# SOM_Resets_BootConfig.net
KiCad netlist of a schematic drawn in Altium Designer
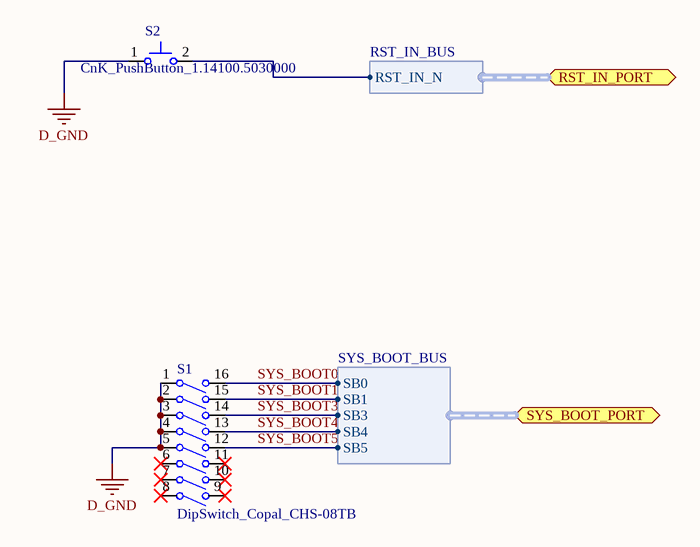
[diagram p0: SOM_Resets_BootConfig.SchDoc]

(export (version "E")
  (design (tool "Eeschema 10.0.6"))
  (components
    (comp (ref "S1")
      (value "DipSwitch_Copal_CHS-08TB")
      (footprint "SOP127P800X250-16N_DIP_SWITCH_COPAL:SOP127P800X250-16N_DIP_SWITCH_COPAL")
      (fields (field (name "PUBLISHER") "Altium Limited"))
      (libsource (lib "OMRON Switch DIP") (part "A6H-8102-P"))
    )
    (comp (ref "S2")
      (value "CnK_PushButton_1.14100.5030000")
      (footprint "SOP127P600-8N_PushButtonRacon8:SOP127P600-8N_PushButtonRacon8")
      (fields (field (name "PUBLISHER") "Altium Limited"))
      (libsource (lib "CK Switch") (part "KSS222GLFG"))
    )
  )
  (nets
    (net (code "3") (name "/RST_IN_N") (class "Default")
      (node (ref "S2") (pin "2") (pinfunction "2_2") (pintype "passive"))
    )
    (net (code "4") (name "/SYS_BOOT0") (class "Default")
      (node (ref "S1") (pin "16") (pinfunction "B1_16") (pintype "passive"))
    )
    (net (code "5") (name "/SYS_BOOT1") (class "Default")
      (node (ref "S1") (pin "15") (pinfunction "B2_15") (pintype "passive"))
    )
    (net (code "6") (name "/SYS_BOOT3") (class "Default")
      (node (ref "S1") (pin "14") (pinfunction "B3_14") (pintype "passive"))
    )
    (net (code "7") (name "/SYS_BOOT4") (class "Default")
      (node (ref "S1") (pin "13") (pinfunction "B4_13") (pintype "passive"))
    )
    (net (code "8") (name "/SYS_BOOT5") (class "Default")
      (node (ref "S1") (pin "12") (pinfunction "B5_12") (pintype "passive"))
    )
    (net (code "11") (name "D_GND") (class "Default")
      (node (ref "S1") (pin "1") (pinfunction "A1_1") (pintype "passive"))
      (node (ref "S1") (pin "2") (pinfunction "A2_2") (pintype "passive"))
      (node (ref "S1") (pin "3") (pinfunction "A3_3") (pintype "passive"))
      (node (ref "S1") (pin "4") (pinfunction "A4_4") (pintype "passive"))
      (node (ref "S1") (pin "5") (pinfunction "A5_5") (pintype "passive"))
      (node (ref "S2") (pin "1") (pinfunction "1_1") (pintype "passive"))
    )
    (net (code "12") (name "unconnected-(S1-A6-Pad6)") (class "Default")
      (node (ref "S1") (pin "6") (pinfunction "A6_6") (pintype "passive+no_connect"))
    )
    (net (code "13") (name "unconnected-(S1-A7-Pad7)") (class "Default")
      (node (ref "S1") (pin "7") (pinfunction "A7_7") (pintype "passive+no_connect"))
    )
    (net (code "14") (name "unconnected-(S1-A8-Pad8)") (class "Default")
      (node (ref "S1") (pin "8") (pinfunction "A8_8") (pintype "passive+no_connect"))
    )
    (net (code "15") (name "unconnected-(S1-B6-Pad11)") (class "Default")
      (node (ref "S1") (pin "11") (pinfunction "B6_11") (pintype "passive+no_connect"))
    )
    (net (code "16") (name "unconnected-(S1-B7-Pad10)") (class "Default")
      (node (ref "S1") (pin "10") (pinfunction "B7_10") (pintype "passive+no_connect"))
    )
    (net (code "17") (name "unconnected-(S1-B8-Pad9)") (class "Default")
      (node (ref "S1") (pin "9") (pinfunction "B8_9") (pintype "passive+no_connect"))
    )
  )
)
